# DK_GU600E_V10.net
KiCad netlist of a schematic drawn in Altium Designer
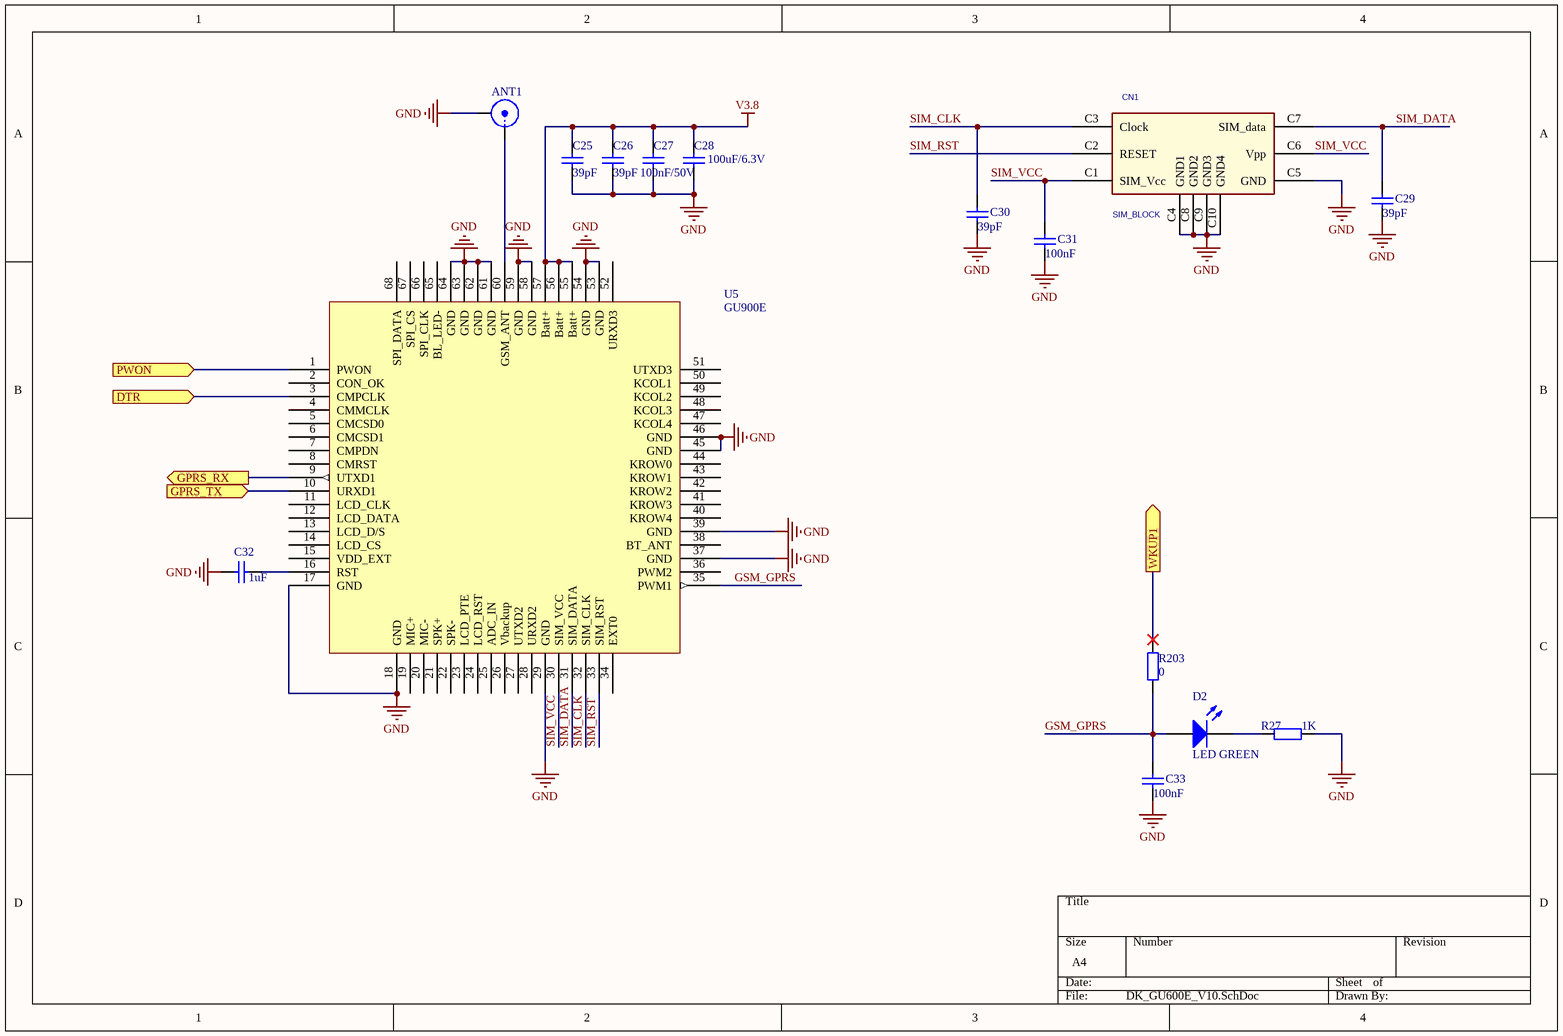
[diagram p0: DK_GU600E_V10.SchDoc]

(export (version "E")
  (design (tool "Eeschema 10.0.6"))
  (components
    (comp (ref "ANT1")
      (value "SMB")
      (footprint "SMB_V-RJ45")
      (description "SMB Straight Connector")
      (fields (field (name "PUBLISHER") "Altium Limited"))
      (libsource (lib "Miscellaneous Connectors") (part "SMB"))
    )
    (comp (ref "C25")
      (value "39pF")
      (footprint "0603")
      (description "Capacitor")
      (fields (field (name "Comment") "Cap") (field (name "PUBLISHER") "Altium Limited"))
      (libsource (lib "Miscellaneous Devices") (part "Cap"))
    )
    (comp (ref "C26")
      (value "39pF")
      (footprint "0603")
      (description "Capacitor")
      (fields (field (name "Comment") "Cap") (field (name "PUBLISHER") "Altium Limited"))
      (libsource (lib "Miscellaneous Devices") (part "Cap"))
    )
    (comp (ref "C27")
      (value "100nF/50V")
      (footprint "0603")
      (description "Capacitor")
      (fields (field (name "Comment") "Cap") (field (name "PUBLISHER") "Altium Limited"))
      (libsource (lib "Miscellaneous Devices") (part "Cap"))
    )
    (comp (ref "C28")
      (value "100uF/6.3V")
      (footprint "LC-CASE-D_7343")
      (description "Capacitor")
      (fields (field (name "Comment") "Cap") (field (name "PUBLISHER") "Altium Limited"))
      (libsource (lib "Miscellaneous Devices") (part "Cap"))
    )
    (comp (ref "C29")
      (value "39pF")
      (footprint "0603")
      (description "Capacitor")
      (fields (field (name "Comment") "Cap") (field (name "PUBLISHER") "Altium Limited"))
      (libsource (lib "Miscellaneous Devices") (part "Cap"))
    )
    (comp (ref "C30")
      (value "39pF")
      (footprint "0603")
      (description "Capacitor")
      (fields (field (name "Comment") "Cap") (field (name "PUBLISHER") "Altium Limited"))
      (libsource (lib "Miscellaneous Devices") (part "Cap"))
    )
    (comp (ref "C31")
      (value "100nF")
      (footprint "0603")
      (description "Capacitor")
      (fields (field (name "Comment") "Cap") (field (name "PUBLISHER") "Altium Limited"))
      (libsource (lib "Miscellaneous Devices") (part "Cap"))
    )
    (comp (ref "C32")
      (value "1uF")
      (footprint "0603")
      (description "Capacitor")
      (fields (field (name "Comment") "Cap") (field (name "PUBLISHER") "Altium Limited"))
      (libsource (lib "Miscellaneous Devices") (part "Cap"))
    )
    (comp (ref "C33")
      (value "100nF")
      (footprint "0603")
      (description "Capacitor")
      (fields (field (name "Comment") "Cap") (field (name "PUBLISHER") "Altium Limited"))
      (libsource (lib "Miscellaneous Devices") (part "Cap"))
    )
    (comp (ref "CN1")
      (value "SIM_BLOCK")
      (footprint "SIM_BLOCK")
      (libsource (lib "TB906") (part "SIM_BLOCK_2"))
    )
    (comp (ref "D2")
      (value "LED GREEN")
      (footprint "LED0603")
      (description "Typical RED, GREEN, YELLOW, AMBER GaAs LED")
      (fields (field (name "PUBLISHER") "Altium Limited"))
      (libsource (lib "Miscellaneous Devices") (part "LED2"))
    )
    (comp (ref "R27")
      (value "1K")
      (footprint "0603")
      (description "Resistor")
      (fields (field (name "Comment") "Res2") (field (name "PUBLISHER") "Altium Limited"))
      (libsource (lib "") (part "Res2_1"))
    )
    (comp (ref "R203")
      (value "0")
      (footprint "0603")
      (description "Resistor")
      (fields (field (name "Comment") "Res2") (field (name "PUBLISHER") "Altium Limited"))
      (libsource (lib "Miscellaneous Devices") (part "Res2"))
    )
    (comp (ref "U5") (value "GU900E") (footprint "SIM900-68P") (libsource (lib "GU900E") (part "GU900E")))
  )
  (nets
    (net (code "1") (name "/DTR") (class "Default")
      (node (ref "U5") (pin "3") (pinfunction "CMPCLK_3") (pintype "passive"))
    )
    (net (code "2") (name "/GPRS_RX") (class "Default")
      (node (ref "U5") (pin "9") (pinfunction "UTXD1_9") (pintype "output"))
    )
    (net (code "3") (name "/GPRS_TX") (class "Default")
      (node (ref "U5") (pin "10") (pinfunction "URXD1_10") (pintype "passive"))
    )
    (net (code "4") (name "/GSM_GPRS") (class "Default")
      (node (ref "C33") (pin "2") (pinfunction "2_2") (pintype "passive"))
      (node (ref "D2") (pin "1") (pinfunction "A_1") (pintype "passive"))
      (node (ref "R203") (pin "1") (pinfunction "1_1") (pintype "passive"))
      (node (ref "U5") (pin "35") (pinfunction "PWM1_35") (pintype "output"))
    )
    (net (code "5") (name "/PWON") (class "Default")
      (node (ref "U5") (pin "1") (pinfunction "PWON_1") (pintype "passive"))
    )
    (net (code "6") (name "/SIM_CLK") (class "Default")
      (node (ref "C30") (pin "2") (pinfunction "2_2") (pintype "passive"))
      (node (ref "CN1") (pin "C3") (pinfunction "Clock_C3") (pintype "passive"))
      (node (ref "U5") (pin "32") (pinfunction "SIM_CLK_32") (pintype "passive"))
    )
    (net (code "7") (name "/SIM_DATA") (class "Default")
      (node (ref "C29") (pin "2") (pinfunction "2_2") (pintype "passive"))
      (node (ref "CN1") (pin "C7") (pinfunction "SIM_data_C7") (pintype "passive"))
      (node (ref "U5") (pin "31") (pinfunction "SIM_DATA_31") (pintype "passive"))
    )
    (net (code "8") (name "/SIM_RST") (class "Default")
      (node (ref "CN1") (pin "C2") (pinfunction "RESET_C2") (pintype "passive"))
      (node (ref "U5") (pin "33") (pinfunction "SIM_RST_33") (pintype "passive"))
    )
    (net (code "9") (name "/SIM_VCC") (class "Default")
      (node (ref "C31") (pin "2") (pinfunction "2_2") (pintype "passive"))
      (node (ref "CN1") (pin "C1") (pinfunction "SIM_Vcc_C1") (pintype "passive"))
      (node (ref "CN1") (pin "C6") (pinfunction "Vpp_C6") (pintype "passive"))
      (node (ref "U5") (pin "30") (pinfunction "SIM_VCC_30") (pintype "passive"))
    )
    (net (code "10") (name "/WKUP1") (class "Default")
      (node (ref "R203") (pin "2") (pinfunction "2_2") (pintype "passive+no_connect"))
    )
    (net (code "11") (name "GND") (class "Default")
      (node (ref "ANT1") (pin "2") (pinfunction "Y_2") (pintype "passive"))
      (node (ref "C25") (pin "1") (pinfunction "1_1") (pintype "passive"))
      (node (ref "C26") (pin "1") (pinfunction "1_1") (pintype "passive"))
      (node (ref "C27") (pin "1") (pinfunction "1_1") (pintype "passive"))
      (node (ref "C28") (pin "1") (pinfunction "1_1") (pintype "passive"))
      (node (ref "C29") (pin "1") (pinfunction "1_1") (pintype "passive"))
      (node (ref "C30") (pin "1") (pinfunction "1_1") (pintype "passive"))
      (node (ref "C31") (pin "1") (pinfunction "1_1") (pintype "passive"))
      (node (ref "C32") (pin "1") (pinfunction "1_1") (pintype "passive"))
      (node (ref "C33") (pin "1") (pinfunction "1_1") (pintype "passive"))
      (node (ref "CN1") (pin "C10") (pinfunction "GND4_C10") (pintype "passive"))
      (node (ref "CN1") (pin "C4") (pinfunction "GND1_C4") (pintype "passive"))
      (node (ref "CN1") (pin "C5") (pinfunction "GND_C5") (pintype "passive"))
      (node (ref "CN1") (pin "C8") (pinfunction "GND2_C8") (pintype "passive"))
      (node (ref "CN1") (pin "C9") (pinfunction "GND3_C9") (pintype "passive"))
      (node (ref "R27") (pin "2") (pinfunction "2_2") (pintype "passive"))
      (node (ref "U5") (pin "17") (pinfunction "GND_17") (pintype "passive"))
      (node (ref "U5") (pin "18") (pinfunction "GND_18") (pintype "passive"))
      (node (ref "U5") (pin "29") (pinfunction "GND_29") (pintype "passive"))
      (node (ref "U5") (pin "37") (pinfunction "GND_37") (pintype "passive"))
      (node (ref "U5") (pin "39") (pinfunction "GND_39") (pintype "passive"))
      (node (ref "U5") (pin "45") (pinfunction "GND_45") (pintype "passive"))
      (node (ref "U5") (pin "46") (pinfunction "GND_46") (pintype "passive"))
      (node (ref "U5") (pin "53") (pinfunction "GND_53") (pintype "passive"))
      (node (ref "U5") (pin "54") (pinfunction "GND_54") (pintype "passive"))
      (node (ref "U5") (pin "58") (pinfunction "GND_58") (pintype "passive"))
      (node (ref "U5") (pin "59") (pinfunction "GND_59") (pintype "passive"))
      (node (ref "U5") (pin "61") (pinfunction "GND_61") (pintype "passive"))
      (node (ref "U5") (pin "62") (pinfunction "GND_62") (pintype "passive"))
      (node (ref "U5") (pin "63") (pinfunction "GND_63") (pintype "passive"))
      (node (ref "U5") (pin "64") (pinfunction "GND_64") (pintype "passive"))
    )
    (net (code "12") (name "Net-(ANT1-X)") (class "Default")
      (node (ref "ANT1") (pin "1") (pinfunction "X_1") (pintype "passive"))
      (node (ref "U5") (pin "60") (pinfunction "GSM_ANT_60") (pintype "passive"))
    )
    (net (code "13") (name "Net-(D2-K)") (class "Default")
      (node (ref "D2") (pin "2") (pinfunction "K_2") (pintype "passive"))
      (node (ref "R27") (pin "1") (pinfunction "1_1") (pintype "passive"))
    )
    (net (code "14") (name "Net-(U5-RST)") (class "Default")
      (node (ref "C32") (pin "2") (pinfunction "2_2") (pintype "passive"))
      (node (ref "U5") (pin "16") (pinfunction "RST_16") (pintype "passive"))
    )
    (net (code "15") (name "V3.8") (class "Default")
      (node (ref "C25") (pin "2") (pinfunction "2_2") (pintype "passive"))
      (node (ref "C26") (pin "2") (pinfunction "2_2") (pintype "passive"))
      (node (ref "C27") (pin "2") (pinfunction "2_2") (pintype "passive"))
      (node (ref "C28") (pin "2") (pinfunction "2_2") (pintype "passive"))
      (node (ref "U5") (pin "55") (pinfunction "Batt+_55") (pintype "passive"))
      (node (ref "U5") (pin "56") (pinfunction "Batt+_56") (pintype "passive"))
      (node (ref "U5") (pin "57") (pinfunction "Batt+_57") (pintype "passive"))
    )
    (net (code "16") (name "unconnected-(U5-ADC_IN-Pad25)") (class "Default")
      (node (ref "U5") (pin "25") (pinfunction "ADC_IN_25") (pintype "passive"))
    )
    (net (code "17") (name "unconnected-(U5-BL_LED--Pad65)") (class "Default")
      (node (ref "U5") (pin "65") (pinfunction "BL_LED-_65") (pintype "passive"))
    )
    (net (code "18") (name "unconnected-(U5-BT_ANT-Pad38)") (class "Default")
      (node (ref "U5") (pin "38") (pinfunction "BT_ANT_38") (pintype "passive"))
    )
    (net (code "19") (name "unconnected-(U5-CMCSD0-Pad5)") (class "Default")
      (node (ref "U5") (pin "5") (pinfunction "CMCSD0_5") (pintype "passive"))
    )
    (net (code "20") (name "unconnected-(U5-CMCSD1-Pad6)") (class "Default")
      (node (ref "U5") (pin "6") (pinfunction "CMCSD1_6") (pintype "passive"))
    )
    (net (code "21") (name "unconnected-(U5-CMMCLK-Pad4)") (class "Default")
      (node (ref "U5") (pin "4") (pinfunction "CMMCLK_4") (pintype "passive"))
    )
    (net (code "22") (name "unconnected-(U5-CMPDN-Pad7)") (class "Default")
      (node (ref "U5") (pin "7") (pinfunction "CMPDN_7") (pintype "passive"))
    )
    (net (code "23") (name "unconnected-(U5-CMRST-Pad8)") (class "Default")
      (node (ref "U5") (pin "8") (pinfunction "CMRST_8") (pintype "passive"))
    )
    (net (code "24") (name "unconnected-(U5-CON_OK-Pad2)") (class "Default")
      (node (ref "U5") (pin "2") (pinfunction "CON_OK_2") (pintype "passive"))
    )
    (net (code "25") (name "unconnected-(U5-EXT0-Pad34)") (class "Default")
      (node (ref "U5") (pin "34") (pinfunction "EXT0_34") (pintype "passive"))
    )
    (net (code "26") (name "unconnected-(U5-KCOL1-Pad50)") (class "Default")
      (node (ref "U5") (pin "50") (pinfunction "KCOL1_50") (pintype "passive"))
    )
    (net (code "27") (name "unconnected-(U5-KCOL2-Pad49)") (class "Default")
      (node (ref "U5") (pin "49") (pinfunction "KCOL2_49") (pintype "passive"))
    )
    (net (code "28") (name "unconnected-(U5-KCOL3-Pad48)") (class "Default")
      (node (ref "U5") (pin "48") (pinfunction "KCOL3_48") (pintype "passive"))
    )
    (net (code "29") (name "unconnected-(U5-KCOL4-Pad47)") (class "Default")
      (node (ref "U5") (pin "47") (pinfunction "KCOL4_47") (pintype "passive"))
    )
    (net (code "30") (name "unconnected-(U5-KROW0-Pad44)") (class "Default")
      (node (ref "U5") (pin "44") (pinfunction "KROW0_44") (pintype "passive"))
    )
    (net (code "31") (name "unconnected-(U5-KROW1-Pad43)") (class "Default")
      (node (ref "U5") (pin "43") (pinfunction "KROW1_43") (pintype "passive"))
    )
    (net (code "32") (name "unconnected-(U5-KROW2-Pad42)") (class "Default")
      (node (ref "U5") (pin "42") (pinfunction "KROW2_42") (pintype "passive"))
    )
    (net (code "33") (name "unconnected-(U5-KROW3-Pad41)") (class "Default")
      (node (ref "U5") (pin "41") (pinfunction "KROW3_41") (pintype "passive"))
    )
    (net (code "34") (name "unconnected-(U5-KROW4-Pad40)") (class "Default")
      (node (ref "U5") (pin "40") (pinfunction "KROW4_40") (pintype "passive"))
    )
    (net (code "35") (name "unconnected-(U5-LCD_CLK-Pad11)") (class "Default")
      (node (ref "U5") (pin "11") (pinfunction "LCD_CLK_11") (pintype "passive"))
    )
    (net (code "36") (name "unconnected-(U5-LCD_CS-Pad14)") (class "Default")
      (node (ref "U5") (pin "14") (pinfunction "LCD_CS_14") (pintype "passive"))
    )
    (net (code "37") (name "unconnected-(U5-LCD_DATA-Pad12)") (class "Default")
      (node (ref "U5") (pin "12") (pinfunction "LCD_DATA_12") (pintype "passive"))
    )
    (net (code "38") (name "unconnected-(U5-LCD_D{slash}S-Pad13)") (class "Default")
      (node (ref "U5") (pin "13") (pinfunction "LCD_D/S_13") (pintype "passive"))
    )
    (net (code "39") (name "unconnected-(U5-LCD_PTE-Pad23)") (class "Default")
      (node (ref "U5") (pin "23") (pinfunction "LCD_PTE_23") (pintype "passive"))
    )
    (net (code "40") (name "unconnected-(U5-LCD_RST-Pad24)") (class "Default")
      (node (ref "U5") (pin "24") (pinfunction "LCD_RST_24") (pintype "passive"))
    )
    (net (code "41") (name "unconnected-(U5-MIC+-Pad19)") (class "Default")
      (node (ref "U5") (pin "19") (pinfunction "MIC+_19") (pintype "passive"))
    )
    (net (code "42") (name "unconnected-(U5-MIC--Pad20)") (class "Default")
      (node (ref "U5") (pin "20") (pinfunction "MIC-_20") (pintype "passive"))
    )
    (net (code "43") (name "unconnected-(U5-PWM2-Pad36)") (class "Default")
      (node (ref "U5") (pin "36") (pinfunction "PWM2_36") (pintype "passive"))
    )
    (net (code "44") (name "unconnected-(U5-SPI_CLK-Pad66)") (class "Default")
      (node (ref "U5") (pin "66") (pinfunction "SPI_CLK_66") (pintype "passive"))
    )
    (net (code "45") (name "unconnected-(U5-SPI_CS-Pad67)") (class "Default")
      (node (ref "U5") (pin "67") (pinfunction "SPI_CS_67") (pintype "passive"))
    )
    (net (code "46") (name "unconnected-(U5-SPI_DATA-Pad68)") (class "Default")
      (node (ref "U5") (pin "68") (pinfunction "SPI_DATA_68") (pintype "passive"))
    )
    (net (code "47") (name "unconnected-(U5-SPK+-Pad21)") (class "Default")
      (node (ref "U5") (pin "21") (pinfunction "SPK+_21") (pintype "passive"))
    )
    (net (code "48") (name "unconnected-(U5-SPK--Pad22)") (class "Default")
      (node (ref "U5") (pin "22") (pinfunction "SPK-_22") (pintype "passive"))
    )
    (net (code "49") (name "unconnected-(U5-URXD2-Pad28)") (class "Default")
      (node (ref "U5") (pin "28") (pinfunction "URXD2_28") (pintype "passive"))
    )
    (net (code "50") (name "unconnected-(U5-URXD3-Pad52)") (class "Default")
      (node (ref "U5") (pin "52") (pinfunction "URXD3_52") (pintype "passive"))
    )
    (net (code "51") (name "unconnected-(U5-UTXD2-Pad27)") (class "Default")
      (node (ref "U5") (pin "27") (pinfunction "UTXD2_27") (pintype "passive"))
    )
    (net (code "52") (name "unconnected-(U5-UTXD3-Pad51)") (class "Default")
      (node (ref "U5") (pin "51") (pinfunction "UTXD3_51") (pintype "passive"))
    )
    (net (code "53") (name "unconnected-(U5-VDD_EXT-Pad15)") (class "Default")
      (node (ref "U5") (pin "15") (pinfunction "VDD_EXT_15") (pintype "passive"))
    )
    (net (code "54") (name "unconnected-(U5-Vbackup-Pad26)") (class "Default")
      (node (ref "U5") (pin "26") (pinfunction "Vbackup_26") (pintype "passive"))
    )
  )
)
